# SUP_2_5_FMC.net
KiCad netlist of a schematic drawn in Altium Designer
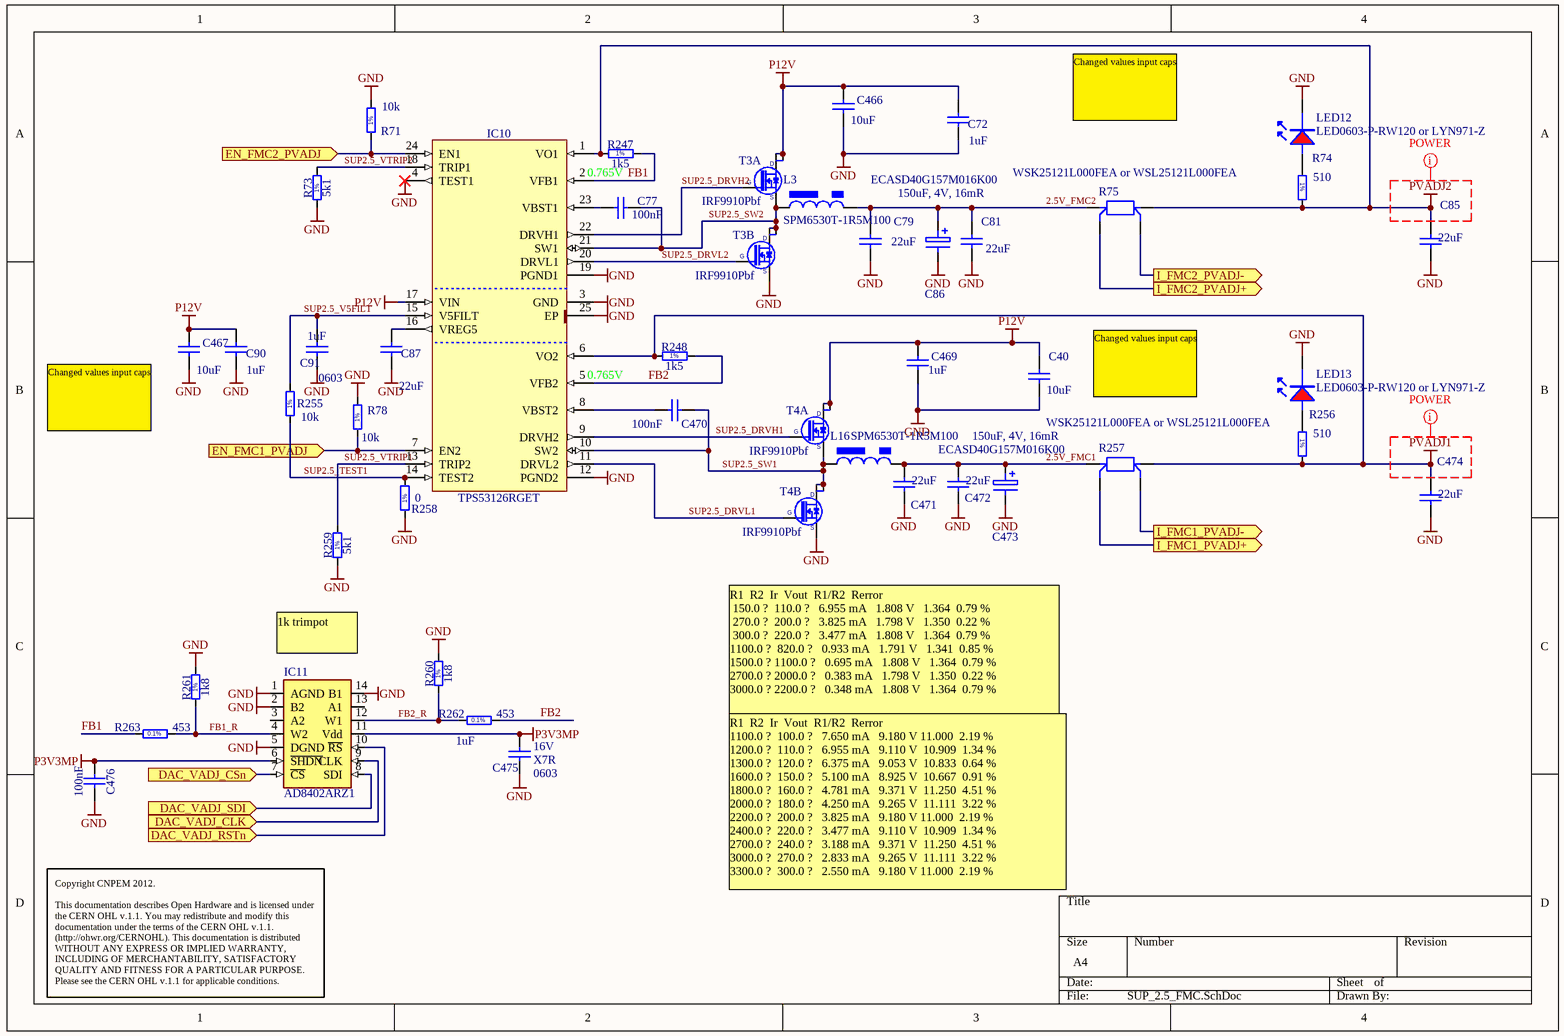
[diagram p0: SUP_2.5_FMC.SchDoc]

(export (version "E")
  (design (tool "Eeschema 10.0.6"))
  (components
    (comp (ref "C40")
      (value "10uF")
      (footprint "CAPC2012X135N")
      (description "Non-polarised capacitor")
      (fields
        (field (name "PART NUMBER") "CC0805_10UF_16V_10%_X5R")
        (field (name "VOLTAGE") "16V")
        (field (name "AUTHOR") "CERN DEM JLC")
      )
      (libsource (lib "Capacitors") (part "Capacitor - non polarized"))
    )
    (comp (ref "C72")
      (value "1uF")
      (footprint "CAPC1608X87N")
      (description "Non-polarised capacitor")
      (fields
        (field (name "PART NUMBER") "CC0603_1UF_16V_10%_X7R")
        (field (name "VOLTAGE") "16V")
        (field (name "AUTHOR") "CERN DEM JLC")
      )
      (libsource (lib "Capacitors") (part "Capacitor - non polarized"))
    )
    (comp (ref "C77")
      (value "100nF")
      (footprint "CAPC1005X55N")
      (description "Non-polarised capacitor")
      (fields
        (field (name "PART NUMBER") "CC0402_100NF_16V_10%_X7R")
        (field (name "VOLTAGE") "16V")
        (field (name "AUTHOR") "CERN DEM JLC")
      )
      (libsource (lib "Capacitors") (part "Capacitor - non polarized"))
    )
    (comp (ref "C79")
      (value "22uF")
      (footprint "CAPC3216X180N")
      (description "Non-polarised capacitor")
      (fields
        (field (name "PART NUMBER") "CC1206_22UF_10V_10%_X7R")
        (field (name "VOLTAGE") "10V")
        (field (name "AUTHOR") "CERN DEM JLC")
      )
      (libsource (lib "Capacitors") (part "Capacitor - non polarized"))
    )
    (comp (ref "C81")
      (value "22uF")
      (footprint "CAPC3216X180N")
      (description "Non-polarised capacitor")
      (fields
        (field (name "PART NUMBER") "CC1206_22UF_10V_10%_X7R")
        (field (name "VOLTAGE") "10V")
        (field (name "AUTHOR") "CERN DEM JLC")
      )
      (libsource (lib "Capacitors") (part "Capacitor - non polarized"))
    )
    (comp (ref "C85")
      (value "22uF")
      (footprint "CAPC3216X180N")
      (description "Non-polarised capacitor")
      (fields
        (field (name "PART NUMBER") "CC1206_22UF_10V_10%_X7R")
        (field (name "VOLTAGE") "10V")
        (field (name "AUTHOR") "CERN DEM JLC")
      )
      (libsource (lib "Capacitors") (part "Capacitor - non polarized"))
    )
    (comp (ref "C86")
      (value "ECASD40G157M016K00")
      (footprint "2917_POLY")
      (description "POLY, 150uF, 4V, ESR: 16mR")
      (fields (field (name "ALTIUM_VALUE") "150uF, 4V, 16mR"))
      (libsource (lib "LIBRARY_SCH") (part "CAP_POLYMER_SMDD"))
    )
    (comp (ref "C87")
      (value "22uF")
      (footprint "CAPC3216X180N")
      (description "Non-polarised capacitor")
      (fields
        (field (name "PART NUMBER") "CC1206_22UF_10V_10%_X7R")
        (field (name "VOLTAGE") "10V")
        (field (name "AUTHOR") "CERN DEM JLC")
      )
      (libsource (lib "Capacitors") (part "Capacitor - non polarized"))
    )
    (comp (ref "C90")
      (value "1uF")
      (footprint "CAPC1608X87N")
      (description "Non-polarised capacitor")
      (fields
        (field (name "PART NUMBER") "CC0603_1UF_16V_10%_X7R")
        (field (name "VOLTAGE") "16V")
        (field (name "AUTHOR") "CERN DEM JLC")
      )
      (libsource (lib "Capacitors") (part "Capacitor - non polarized"))
    )
    (comp (ref "C91")
      (value "1uF")
      (footprint "CAPC1608X87N")
      (description "Non-polarised capacitor")
      (fields
        (field (name "PART NUMBER") "CC0603_1UF_16V_10%_X7R")
        (field (name "VOLTAGE") "16V")
        (field (name "CASE") "0603")
        (field (name "AUTHOR") "CERN DEM JLC")
      )
      (libsource (lib "Capacitors") (part "Capacitor - non polarized"))
    )
    (comp (ref "C466")
      (value "10uF")
      (footprint "CAPC2012X135N")
      (description "Non-polarised capacitor")
      (fields
        (field (name "PART NUMBER") "CC0805_10UF_16V_10%_X5R")
        (field (name "VOLTAGE") "16V")
        (field (name "AUTHOR") "CERN DEM JLC")
      )
      (libsource (lib "Capacitors") (part "Capacitor - non polarized"))
    )
    (comp (ref "C467")
      (value "10uF")
      (footprint "CAPC2012X135N")
      (description "Non-polarised capacitor")
      (fields
        (field (name "PART NUMBER") "CC0805_10UF_16V_10%_X5R")
        (field (name "VOLTAGE") "16V")
        (field (name "AUTHOR") "CERN DEM JLC")
      )
      (libsource (lib "Capacitors") (part "Capacitor - non polarized"))
    )
    (comp (ref "C469")
      (value "1uF")
      (footprint "CAPC1608X87N")
      (description "Non-polarised capacitor")
      (fields
        (field (name "PART NUMBER") "CC0603_1UF_16V_10%_X7R")
        (field (name "VOLTAGE") "16V")
        (field (name "AUTHOR") "CERN DEM JLC")
      )
      (libsource (lib "Capacitors") (part "Capacitor - non polarized"))
    )
    (comp (ref "C470")
      (value "100nF")
      (footprint "CAPC1005X55N")
      (description "Non-polarised capacitor")
      (fields
        (field (name "PART NUMBER") "CC0402_100NF_16V_10%_X7R")
        (field (name "VOLTAGE") "16V")
        (field (name "AUTHOR") "CERN DEM JLC")
      )
      (libsource (lib "Capacitors") (part "Capacitor - non polarized"))
    )
    (comp (ref "C471")
      (value "22uF")
      (footprint "CAPC3216X180N")
      (description "Non-polarised capacitor")
      (fields
        (field (name "PART NUMBER") "CC1206_22UF_10V_10%_X7R")
        (field (name "VOLTAGE") "10V")
        (field (name "AUTHOR") "CERN DEM JLC")
      )
      (libsource (lib "Capacitors") (part "Capacitor - non polarized"))
    )
    (comp (ref "C472")
      (value "22uF")
      (footprint "CAPC3216X180N")
      (description "Non-polarised capacitor")
      (fields
        (field (name "PART NUMBER") "CC1206_22UF_10V_10%_X7R")
        (field (name "VOLTAGE") "10V")
        (field (name "AUTHOR") "CERN DEM JLC")
      )
      (libsource (lib "Capacitors") (part "Capacitor - non polarized"))
    )
    (comp (ref "C473")
      (value "ECASD40G157M016K00")
      (footprint "2917_POLY")
      (description "POLY, 150uF, 4V, ESR: 16mR")
      (fields (field (name "ALTIUM_VALUE") "150uF, 4V, 16mR"))
      (libsource (lib "LIBRARY_SCH") (part "CAP_POLYMER_SMDD"))
    )
    (comp (ref "C474")
      (value "22uF")
      (footprint "CAPC3216X180N")
      (description "Non-polarised capacitor")
      (fields
        (field (name "PART NUMBER") "CC1206_22UF_10V_10%_X7R")
        (field (name "VOLTAGE") "10V")
        (field (name "AUTHOR") "CERN DEM JLC")
      )
      (libsource (lib "Capacitors") (part "Capacitor - non polarized"))
    )
    (comp (ref "C475")
      (value "1uF")
      (footprint "CAPC1608X87N")
      (description "Non-polarised capacitor")
      (fields
        (field (name "PART NUMBER") "CC0603_1UF_16V_10%_X7R")
        (field (name "VOLTAGE") "16V")
        (field (name "TC") "X7R")
        (field (name "TOLERANCE") "±10%")
        (field (name "CASE") "0603")
        (field (name "AUTHOR") "CERN DEM JLC")
      )
      (libsource (lib "Capacitors") (part "Capacitor - non polarized"))
    )
    (comp (ref "C476")
      (value "100nF")
      (footprint "CAPC0603X33N")
      (description "Non-polarised capacitor")
      (fields
        (field (name "PART NUMBER") "CC0201_100NF_6.3V_10%_X5R")
        (field (name "VOLTAGE") "6.3V")
        (field (name "AUTHOR") "CERN DEM JLC")
      )
      (libsource (lib "Capacitors") (part "Capacitor - non polarized"))
    )
    (comp (ref "IC10")
      (value "TPS53126RGET")
      (footprint "QFN50P400X400X100-25N-S255")
      (description "Dual Synchronous Step-Down Controller For Low Voltage Power Rails")
      (fields (field (name "MANUFACTURER") "TEXAS INSTRUMENTS") (field (name "AUTHOR") "CERN DEM JLC"))
      (libsource (lib "ICs And Semiconductors") (part "TPS53126RGET"))
    )
    (comp (ref "IC11")
      (value "AD8402ARZ1")
      (footprint "SO-14")
      (description "1k dual digital potentiometer")
      (libsource (lib "LIBRARY_SCH") (part "DAC_AD8402"))
    )
    (comp (ref "L3")
      (value "SPM6530T-1R5M100")
      (footprint "IND_TDK_SPM6530")
      (description "1.5uH, 20%, 10mR, 11.5A")
      (libsource (lib "LIBRARY_SCH") (part "L_POWER_SPM6530T"))
    )
    (comp (ref "L16")
      (value "SPM6530T-1R5M100")
      (footprint "IND_TDK_SPM6530")
      (description "1.5uH, 20%, 10mR, 11.5A")
      (libsource (lib "LIBRARY_SCH") (part "L_POWER_SPM6530T"))
    )
    (comp (ref "LED12")
      (value "LED0603-P-RW120 or LYN971-Z")
      (footprint "led_0603R")
      (description "LED 0603 red")
      (libsource (lib "LIBRARY_SCH") (part "LED_0603R"))
    )
    (comp (ref "LED13")
      (value "LED0603-P-RW120 or LYN971-Z")
      (footprint "led_0603R")
      (description "LED 0603 red")
      (libsource (lib "LIBRARY_SCH") (part "LED_0603R"))
    )
    (comp (ref "R71")
      (value "10k")
      (footprint "RESC1005X40N")
      (description "Resistor - 1%")
      (fields
        (field (name "PART NUMBER") "R0402_10K_1%_0.0625W_100PPM")
        (field (name "POWER") "0.0625W")
        (field (name "AUTHOR") "CERN DEM JLC")
      )
      (libsource (lib "Resistors") (part "Resistor - 1%"))
    )
    (comp (ref "R73")
      (value "5k1")
      (footprint "RESC1608X55N")
      (description "Resistor - 1%")
      (fields
        (field (name "PART NUMBER") "R0603_5K1_1%_0.1W_100PPM")
        (field (name "POWER") "0.1W")
        (field (name "AUTHOR") "CERN DEM JLC")
      )
      (libsource (lib "Resistors") (part "Resistor - 1%"))
    )
    (comp (ref "R74")
      (value "510")
      (footprint "RESC1005X40N")
      (description "Resistor - 1%")
      (fields
        (field (name "PART NUMBER") "R0402_510R_1%_0.0625W_100PPM")
        (field (name "POWER") "0.0625W")
        (field (name "AUTHOR") "CERN DEM JLC")
      )
      (libsource (lib "Resistors") (part "Resistor - 1%"))
    )
    (comp (ref "R75")
      (value "WSK25121L000FEA or WSL25121L000FEA")
      (footprint "RES_WSK2512")
      (description "RESISTOR, METAL STRIP, 0.001 OHM 1%")
      (libsource (lib "LIBRARY_SCH") (part "RES_POW_Kelvin"))
    )
    (comp (ref "R78")
      (value "10k")
      (footprint "RESC1005X40N")
      (description "Resistor - 1%")
      (fields
        (field (name "PART NUMBER") "R0402_10K_1%_0.0625W_100PPM")
        (field (name "POWER") "0.0625W")
        (field (name "AUTHOR") "CERN DEM JLC")
      )
      (libsource (lib "Resistors") (part "Resistor - 1%"))
    )
    (comp (ref "R247")
      (value "1k5")
      (footprint "RESC1608X55N")
      (description "Resistor - 1%")
      (fields
        (field (name "PART NUMBER") "R0603_1K5_1%_0.1W_100PPM")
        (field (name "POWER") "0.1W")
        (field (name "AUTHOR") "CERN DEM JLC")
      )
      (libsource (lib "Resistors") (part "Resistor - 1%"))
    )
    (comp (ref "R248")
      (value "1k5")
      (footprint "RESC1608X55N")
      (description "Resistor - 1%")
      (fields
        (field (name "PART NUMBER") "R0603_1K5_1%_0.1W_100PPM")
        (field (name "POWER") "0.1W")
        (field (name "AUTHOR") "CERN DEM JLC")
      )
      (libsource (lib "Resistors") (part "Resistor - 1%"))
    )
    (comp (ref "R255")
      (value "10k")
      (footprint "RESC1005X40N")
      (description "Resistor - 1%")
      (fields
        (field (name "PART NUMBER") "R0402_10K_1%_0.0625W_100PPM")
        (field (name "POWER") "0.0625W")
        (field (name "AUTHOR") "CERN DEM JLC")
      )
      (libsource (lib "Resistors") (part "Resistor - 1%"))
    )
    (comp (ref "R256")
      (value "510")
      (footprint "RESC1005X40N")
      (description "Resistor - 1%")
      (fields
        (field (name "PART NUMBER") "R0402_510R_1%_0.0625W_100PPM")
        (field (name "POWER") "0.0625W")
        (field (name "AUTHOR") "CERN DEM JLC")
      )
      (libsource (lib "Resistors") (part "Resistor - 1%"))
    )
    (comp (ref "R257")
      (value "WSK25121L000FEA or WSL25121L000FEA")
      (footprint "RES_WSK2512")
      (description "RESISTOR, METAL STRIP, 0.001 OHM 1%")
      (libsource (lib "LIBRARY_SCH") (part "RES_POW_Kelvin"))
    )
    (comp (ref "R258")
      (value "0")
      (footprint "RESC1005X40N")
      (description "Resistor - 1%")
      (fields
        (field (name "PART NUMBER") "R0402_0R_JUMPER")
        (field (name "MANUFACTURER") "GENERIC")
        (field (name "AUTHOR") "CERN DEM JLC")
      )
      (libsource (lib "Resistors") (part "Resistor - 1%"))
    )
    (comp (ref "R259")
      (value "5k1")
      (footprint "RESC1608X55N")
      (description "Resistor - 1%")
      (fields
        (field (name "PART NUMBER") "R0603_5K1_1%_0.1W_100PPM")
        (field (name "POWER") "0.1W")
        (field (name "AUTHOR") "CERN DEM JLC")
      )
      (libsource (lib "Resistors") (part "Resistor - 1%"))
    )
    (comp (ref "R260")
      (value "1k8")
      (footprint "RESC1608X55N")
      (description "Resistor - 1%")
      (fields
        (field (name "PART NUMBER") "R0603_910R_1%_0.1W_100PPM")
        (field (name "POWER") "0.1W")
        (field (name "AUTHOR") "CERN DEM JLC")
      )
      (libsource (lib "Resistors") (part "Resistor - 1%"))
    )
    (comp (ref "R261")
      (value "1k8")
      (footprint "RESC1608X55N")
      (description "Resistor - 1%")
      (fields
        (field (name "PART NUMBER") "R0603_910R_1%_0.1W_100PPM")
        (field (name "POWER") "0.1W")
        (field (name "AUTHOR") "CERN DEM JLC")
      )
      (libsource (lib "Resistors") (part "Resistor - 1%"))
    )
    (comp (ref "R262")
      (value "453")
      (footprint "RESC1608X55N")
      (description "Resistor - 0.1%")
      (fields
        (field (name "PART NUMBER") "R0603_453R_0.1%_0.063W_10PPM")
        (field (name "POWER") "0.063W")
        (field (name "AUTHOR") "CERN DEM JLC")
      )
      (libsource (lib "Resistors") (part "Resistor - 0.1%"))
    )
    (comp (ref "R263")
      (value "453")
      (footprint "RESC1608X55N")
      (description "Resistor - 0.1%")
      (fields
        (field (name "PART NUMBER") "R0603_453R_0.1%_0.063W_10PPM")
        (field (name "POWER") "0.063W")
        (field (name "AUTHOR") "CERN DEM JLC")
      )
      (libsource (lib "Resistors") (part "Resistor - 0.1%"))
    )
    (comp (ref "T3")
      (value "IRF9910Pbf")
      (footprint "SOIC127P600X175-8N")
      (description "Dual SO-8 MOSFET For POL Cconverter")
      (fields (field (name "MANUFACTURER") "INTERNATIONAL RECTIFIER") (field (name "AUTHOR") "CERN DEM JLC"))
      (libsource (lib "ICs And Semiconductors") (part "IRF9910"))
    )
    (comp (ref "T4")
      (value "IRF9910Pbf")
      (footprint "SOIC127P600X175-8N")
      (description "Dual SO-8 MOSFET For POL Cconverter")
      (fields (field (name "MANUFACTURER") "INTERNATIONAL RECTIFIER") (field (name "AUTHOR") "CERN DEM JLC"))
      (libsource (lib "ICs And Semiconductors") (part "IRF9910"))
    )
  )
  (nets
    (net (code "1") (name "/2.5V_FMC1") (class "Default")
      (node (ref "C471") (pin "1") (pinfunction "1_1") (pintype "passive"))
      (node (ref "C472") (pin "1") (pinfunction "1_1") (pintype "passive"))
      (node (ref "C473") (pin "1") (pinfunction "1_1") (pintype "passive"))
      (node (ref "L16") (pin "2") (pintype "passive"))
      (node (ref "R257") (pin "1") (pinfunction "1_1") (pintype "passive"))
    )
    (net (code "2") (name "/2.5V_FMC2") (class "Default")
      (node (ref "C79") (pin "1") (pinfunction "1_1") (pintype "passive"))
      (node (ref "C81") (pin "1") (pinfunction "1_1") (pintype "passive"))
      (node (ref "C86") (pin "1") (pinfunction "1_1") (pintype "passive"))
      (node (ref "L3") (pin "2") (pintype "passive"))
      (node (ref "R75") (pin "1") (pinfunction "1_1") (pintype "passive"))
    )
    (net (code "3") (name "/DAC_VADJ_CLK") (class "Default")
      (node (ref "IC11") (pin "9") (pinfunction "CLK_9") (pintype "input"))
    )
    (net (code "4") (name "/DAC_VADJ_CSn") (class "Default")
      (node (ref "IC11") (pin "7") (pinfunction "~{CS}_7") (pintype "input"))
    )
    (net (code "5") (name "/DAC_VADJ_RSTn") (class "Default")
      (node (ref "IC11") (pin "10") (pinfunction "~{RS}_10") (pintype "input"))
    )
    (net (code "6") (name "/DAC_VADJ_SDI") (class "Default")
      (node (ref "IC11") (pin "8") (pinfunction "SDI_8") (pintype "input"))
    )
    (net (code "7") (name "/EN_FMC1_PVADJ") (class "Default")
      (node (ref "IC10") (pin "7") (pinfunction "EN2_7") (pintype "input"))
      (node (ref "R78") (pin "1") (pinfunction "1_1") (pintype "passive"))
    )
    (net (code "8") (name "/EN_FMC2_PVADJ") (class "Default")
      (node (ref "IC10") (pin "24") (pinfunction "EN1_24") (pintype "input"))
      (node (ref "R71") (pin "1") (pinfunction "1_1") (pintype "passive"))
    )
    (net (code "9") (name "/FB1") (class "Default")
      (node (ref "IC10") (pin "2") (pinfunction "VFB1_2") (pintype "input"))
      (node (ref "R247") (pin "2") (pinfunction "2_2") (pintype "passive"))
      (node (ref "R263") (pin "1") (pinfunction "1_1") (pintype "passive"))
    )
    (net (code "10") (name "/FB1_R") (class "Default")
      (node (ref "IC11") (pin "4") (pinfunction "W2_4") (pintype "passive"))
      (node (ref "R261") (pin "1") (pinfunction "1_1") (pintype "passive"))
      (node (ref "R263") (pin "2") (pinfunction "2_2") (pintype "passive"))
    )
    (net (code "11") (name "/FB2") (class "Default")
      (node (ref "IC10") (pin "5") (pinfunction "VFB2_5") (pintype "input"))
      (node (ref "R248") (pin "2") (pinfunction "2_2") (pintype "passive"))
      (node (ref "R262") (pin "2") (pinfunction "2_2") (pintype "passive"))
    )
    (net (code "12") (name "/FB2_R") (class "Default")
      (node (ref "IC11") (pin "12") (pinfunction "W1_12") (pintype "passive"))
      (node (ref "R260") (pin "1") (pinfunction "1_1") (pintype "passive"))
      (node (ref "R262") (pin "1") (pinfunction "1_1") (pintype "passive"))
    )
    (net (code "13") (name "/I_FMC1_PVADJ+") (class "Default")
      (node (ref "R257") (pin "1a") (pinfunction "1a_1a") (pintype "passive"))
    )
    (net (code "14") (name "/I_FMC1_PVADJ-") (class "Default")
      (node (ref "R257") (pin "2a") (pinfunction "2a_2a") (pintype "passive"))
    )
    (net (code "15") (name "/I_FMC2_PVADJ+") (class "Default")
      (node (ref "R75") (pin "1a") (pinfunction "1a_1a") (pintype "passive"))
    )
    (net (code "16") (name "/I_FMC2_PVADJ-") (class "Default")
      (node (ref "R75") (pin "2a") (pinfunction "2a_2a") (pintype "passive"))
    )
    (net (code "17") (name "/SUP2.5_DRVH1") (class "Default")
      (node (ref "IC10") (pin "9") (pinfunction "DRVH2_9") (pintype "output"))
      (node (ref "T4") (pin "4") (pinfunction "G_4") (pintype "passive"))
    )
    (net (code "18") (name "/SUP2.5_DRVH2") (class "Default")
      (node (ref "IC10") (pin "22") (pinfunction "DRVH1_22") (pintype "output"))
      (node (ref "T3") (pin "4") (pinfunction "G_4") (pintype "passive"))
    )
    (net (code "19") (name "/SUP2.5_DRVL1") (class "Default")
      (node (ref "IC10") (pin "11") (pinfunction "DRVL2_11") (pintype "output"))
      (node (ref "T4") (pin "2") (pinfunction "G_2") (pintype "passive"))
    )
    (net (code "20") (name "/SUP2.5_DRVL2") (class "Default")
      (node (ref "IC10") (pin "20") (pinfunction "DRVL1_20") (pintype "output"))
      (node (ref "T3") (pin "2") (pinfunction "G_2") (pintype "passive"))
    )
    (net (code "21") (name "/SUP2.5_SW1") (class "Default")
      (node (ref "C470") (pin "1") (pinfunction "1_1") (pintype "passive"))
      (node (ref "IC10") (pin "10") (pinfunction "SW2_10") (pintype "bidirectional"))
      (node (ref "L16") (pin "1") (pintype "passive"))
      (node (ref "T4") (pin "3") (pinfunction "S_3") (pintype "passive"))
      (node (ref "T4") (pin "7") (pinfunction "D_7") (pintype "passive"))
      (node (ref "T4") (pin "8") (pinfunction "D_8") (pintype "passive"))
    )
    (net (code "22") (name "/SUP2.5_SW2") (class "Default")
      (node (ref "C77") (pin "1") (pinfunction "1_1") (pintype "passive"))
      (node (ref "IC10") (pin "21") (pinfunction "SW1_21") (pintype "bidirectional"))
      (node (ref "L3") (pin "1") (pintype "passive"))
      (node (ref "T3") (pin "3") (pinfunction "S_3") (pintype "passive"))
      (node (ref "T3") (pin "7") (pinfunction "D_7") (pintype "passive"))
      (node (ref "T3") (pin "8") (pinfunction "D_8") (pintype "passive"))
    )
    (net (code "23") (name "/SUP2.5_TEST1") (class "Default")
      (node (ref "IC10") (pin "14") (pinfunction "TEST2_14") (pintype "input"))
      (node (ref "R255") (pin "1") (pinfunction "1_1") (pintype "passive"))
      (node (ref "R258") (pin "2") (pinfunction "2_2") (pintype "passive"))
    )
    (net (code "24") (name "/SUP2.5_V5FILT") (class "Default")
      (node (ref "C91") (pin "2") (pinfunction "2_2") (pintype "passive"))
      (node (ref "IC10") (pin "15") (pinfunction "V5FILT_15") (pintype "input"))
      (node (ref "R255") (pin "2") (pinfunction "2_2") (pintype "passive"))
    )
    (net (code "25") (name "/SUP2.5_VTRIP1") (class "Default")
      (node (ref "IC10") (pin "13") (pinfunction "TRIP2_13") (pintype "input"))
      (node (ref "R259") (pin "2") (pinfunction "2_2") (pintype "passive"))
    )
    (net (code "26") (name "/SUP2.5_VTRIP2") (class "Default")
      (node (ref "IC10") (pin "18") (pinfunction "TRIP1_18") (pintype "input"))
      (node (ref "R73") (pin "2") (pinfunction "2_2") (pintype "passive"))
    )
    (net (code "27") (name "GND") (class "Default")
      (node (ref "C40") (pin "1") (pinfunction "1_1") (pintype "passive"))
      (node (ref "C466") (pin "1") (pinfunction "1_1") (pintype "passive"))
      (node (ref "C467") (pin "1") (pinfunction "1_1") (pintype "passive"))
      (node (ref "C469") (pin "1") (pinfunction "1_1") (pintype "passive"))
      (node (ref "C471") (pin "2") (pinfunction "2_2") (pintype "passive"))
      (node (ref "C472") (pin "2") (pinfunction "2_2") (pintype "passive"))
      (node (ref "C473") (pin "2") (pinfunction "2_2") (pintype "passive"))
      (node (ref "C474") (pin "2") (pinfunction "2_2") (pintype "passive"))
      (node (ref "C475") (pin "1") (pinfunction "1_1") (pintype "passive"))
      (node (ref "C476") (pin "2") (pinfunction "2_2") (pintype "passive"))
      (node (ref "C72") (pin "1") (pinfunction "1_1") (pintype "passive"))
      (node (ref "C79") (pin "2") (pinfunction "2_2") (pintype "passive"))
      (node (ref "C81") (pin "2") (pinfunction "2_2") (pintype "passive"))
      (node (ref "C85") (pin "2") (pinfunction "2_2") (pintype "passive"))
      (node (ref "C86") (pin "2") (pinfunction "2_2") (pintype "passive"))
      (node (ref "C87") (pin "1") (pinfunction "1_1") (pintype "passive"))
      (node (ref "C90") (pin "1") (pinfunction "1_1") (pintype "passive"))
      (node (ref "C91") (pin "1") (pinfunction "1_1") (pintype "passive"))
      (node (ref "IC10") (pin "12") (pinfunction "PGND2_12") (pintype "power_in"))
      (node (ref "IC10") (pin "19") (pinfunction "PGND1_19") (pintype "power_in"))
      (node (ref "IC10") (pin "25") (pinfunction "EP_25") (pintype "power_in"))
      (node (ref "IC10") (pin "3") (pinfunction "GND_3") (pintype "power_in"))
      (node (ref "IC10") (pin "4") (pinfunction "TEST1_4") (pintype "output"))
      (node (ref "IC11") (pin "1") (pinfunction "AGND_1") (pintype "power_in"))
      (node (ref "IC11") (pin "14") (pinfunction "B1_14") (pintype "passive"))
      (node (ref "IC11") (pin "2") (pinfunction "B2_2") (pintype "passive"))
      (node (ref "IC11") (pin "5") (pinfunction "DGND_5") (pintype "power_in"))
      (node (ref "LED12") (pin "K") (pinfunction "K_K") (pintype "passive"))
      (node (ref "LED13") (pin "K") (pinfunction "K_K") (pintype "passive"))
      (node (ref "R258") (pin "1") (pinfunction "1_1") (pintype "passive"))
      (node (ref "R259") (pin "1") (pinfunction "1_1") (pintype "passive"))
      (node (ref "R260") (pin "2") (pinfunction "2_2") (pintype "passive"))
      (node (ref "R261") (pin "2") (pinfunction "2_2") (pintype "passive"))
      (node (ref "R71") (pin "2") (pinfunction "2_2") (pintype "passive"))
      (node (ref "R73") (pin "1") (pinfunction "1_1") (pintype "passive"))
      (node (ref "R78") (pin "2") (pinfunction "2_2") (pintype "passive"))
      (node (ref "T3") (pin "1") (pinfunction "S_1") (pintype "passive"))
      (node (ref "T4") (pin "1") (pinfunction "S_1") (pintype "passive"))
    )
    (net (code "28") (name "Net-(IC10-VBST1)") (class "Default")
      (node (ref "C77") (pin "2") (pinfunction "2_2") (pintype "passive"))
      (node (ref "IC10") (pin "23") (pinfunction "VBST1_23") (pintype "input"))
    )
    (net (code "29") (name "Net-(IC10-VBST2)") (class "Default")
      (node (ref "C470") (pin "2") (pinfunction "2_2") (pintype "passive"))
      (node (ref "IC10") (pin "8") (pinfunction "VBST2_8") (pintype "input"))
    )
    (net (code "30") (name "Net-(IC10-VREG5)") (class "Default")
      (node (ref "C87") (pin "2") (pinfunction "2_2") (pintype "passive"))
      (node (ref "IC10") (pin "16") (pinfunction "VREG5_16") (pintype "output"))
    )
    (net (code "31") (name "Net-(LED12-PadA)") (class "Default")
      (node (ref "LED12") (pin "A") (pinfunction "A_A") (pintype "passive"))
      (node (ref "R74") (pin "1") (pinfunction "1_1") (pintype "passive"))
    )
    (net (code "32") (name "Net-(LED13-PadA)") (class "Default")
      (node (ref "LED13") (pin "A") (pinfunction "A_A") (pintype "passive"))
      (node (ref "R256") (pin "1") (pinfunction "1_1") (pintype "passive"))
    )
    (net (code "33") (name "P3V3MP") (class "Default")
      (node (ref "C475") (pin "2") (pinfunction "2_2") (pintype "passive"))
      (node (ref "C476") (pin "1") (pinfunction "1_1") (pintype "passive"))
      (node (ref "IC11") (pin "11") (pinfunction "Vdd_11") (pintype "power_in"))
      (node (ref "IC11") (pin "6") (pinfunction "~{SHDN}_6") (pintype "input"))
    )
    (net (code "34") (name "P12V") (class "Default")
      (node (ref "C40") (pin "2") (pinfunction "2_2") (pintype "passive"))
      (node (ref "C466") (pin "2") (pinfunction "2_2") (pintype "passive"))
      (node (ref "C467") (pin "2") (pinfunction "2_2") (pintype "passive"))
      (node (ref "C469") (pin "2") (pinfunction "2_2") (pintype "passive"))
      (node (ref "C72") (pin "2") (pinfunction "2_2") (pintype "passive"))
      (node (ref "C90") (pin "2") (pinfunction "2_2") (pintype "passive"))
      (node (ref "IC10") (pin "17") (pinfunction "VIN_17") (pintype "input"))
      (node (ref "T3") (pin "5") (pinfunction "D_5") (pintype "passive"))
      (node (ref "T3") (pin "6") (pinfunction "D_6") (pintype "passive"))
      (node (ref "T4") (pin "5") (pinfunction "D_5") (pintype "passive"))
      (node (ref "T4") (pin "6") (pinfunction "D_6") (pintype "passive"))
    )
    (net (code "35") (name "PVADJ1") (class "Default")
      (node (ref "C474") (pin "1") (pinfunction "1_1") (pintype "passive"))
      (node (ref "IC10") (pin "6") (pinfunction "VO2_6") (pintype "input"))
      (node (ref "R248") (pin "1") (pinfunction "1_1") (pintype "passive"))
      (node (ref "R256") (pin "2") (pinfunction "2_2") (pintype "passive"))
      (node (ref "R257") (pin "2") (pinfunction "2_2") (pintype "passive"))
    )
    (net (code "36") (name "PVADJ2") (class "Default")
      (node (ref "C85") (pin "1") (pinfunction "1_1") (pintype "passive"))
      (node (ref "IC10") (pin "1") (pinfunction "VO1_1") (pintype "input"))
      (node (ref "R247") (pin "1") (pinfunction "1_1") (pintype "passive"))
      (node (ref "R74") (pin "2") (pinfunction "2_2") (pintype "passive"))
      (node (ref "R75") (pin "2") (pinfunction "2_2") (pintype "passive"))
    )
    (net (code "37") (name "unconnected-(IC11-A1-Pad13)") (class "Default")
      (node (ref "IC11") (pin "13") (pinfunction "A1_13") (pintype "passive"))
    )
    (net (code "38") (name "unconnected-(IC11-A2-Pad3)") (class "Default")
      (node (ref "IC11") (pin "3") (pinfunction "A2_3") (pintype "passive"))
    )
  )
)
